# MP9361.net
KiCad netlist of a schematic drawn in EAGLE
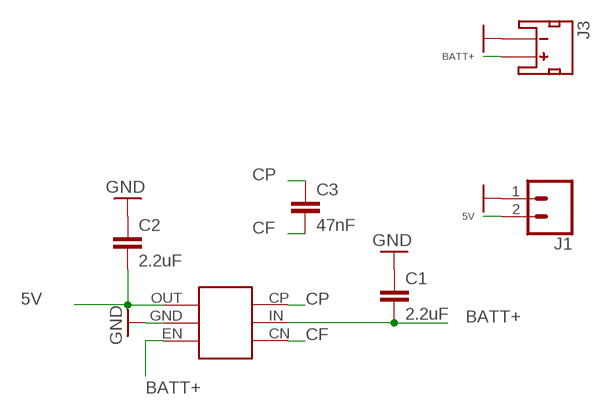
[diagram p0: schematic, sheet 1]

(export (version "E")
  (design (tool "Eeschema 10.0.6"))
  (components
    (comp (ref "C1")
      (value "2.2uF")
      (footprint "eagle-import:0805")
      (libsource (lib "eagle-import") (part "2.2UF-0805-25V-(+80/-20%)"))
    )
    (comp (ref "C2")
      (value "2.2uF")
      (footprint "eagle-import:0805")
      (libsource (lib "eagle-import") (part "2.2UF-0805-25V-(+80/-20%)"))
    )
    (comp (ref "C3")
      (value "47nF")
      (footprint "eagle-import:0603")
      (libsource (lib "eagle-import") (part "47NF-0603-25V-5%"))
    )
    (comp (ref "J1")
      (value "CONN_02PTH4")
      (footprint "eagle-import:1X02_XTRA_BIG")
      (libsource (lib "eagle-import") (part "CONN_02PTH4"))
    )
    (comp (ref "J3")
      (value "Batt Conn")
      (footprint "eagle-import:JST-2-SMD")
      (libsource (lib "eagle-import") (part "JST_2MM_MALE"))
    )
    (comp (ref "U1")
      (value "MP9361")
      (footprint "eagle-import:MP9361")
      (libsource (lib "eagle-import") (part "MP9361"))
    )
  )
  (nets
    (net (code "1") (name "/5V") (class "Default")
      (node (ref "C2") (pin "2") (pinfunction "2_2") (pintype "passive"))
      (node (ref "J1") (pin "2") (pinfunction "2_2") (pintype "passive"))
      (node (ref "U1") (pin "OUT") (pinfunction "OUT_OUT") (pintype "bidirectional"))
    )
    (net (code "2") (name "/BATT+") (class "Default")
      (node (ref "C1") (pin "2") (pinfunction "2_2") (pintype "passive"))
      (node (ref "J3") (pin "2") (pinfunction "+_2") (pintype "bidirectional"))
      (node (ref "U1") (pin "EN") (pinfunction "EN_EN") (pintype "bidirectional"))
      (node (ref "U1") (pin "IN") (pinfunction "IN_IN") (pintype "bidirectional"))
    )
    (net (code "3") (name "/CF") (class "Default")
      (node (ref "C3") (pin "2") (pinfunction "2_2") (pintype "passive"))
      (node (ref "U1") (pin "CN") (pinfunction "CN_CN") (pintype "bidirectional"))
    )
    (net (code "4") (name "/CP") (class "Default")
      (node (ref "C3") (pin "1") (pinfunction "1_1") (pintype "passive"))
      (node (ref "U1") (pin "CP") (pinfunction "CP_CP") (pintype "bidirectional"))
    )
    (net (code "5") (name "GND") (class "Default")
      (node (ref "C1") (pin "1") (pinfunction "1_1") (pintype "passive"))
      (node (ref "C2") (pin "1") (pinfunction "1_1") (pintype "passive"))
      (node (ref "J1") (pin "1") (pinfunction "1_1") (pintype "passive"))
      (node (ref "J3") (pin "1") (pinfunction "-_1") (pintype "bidirectional"))
      (node (ref "U1") (pin "GND") (pinfunction "GND_GND") (pintype "bidirectional"))
    )
    (net (code "6") (name "unconnected-(J3-PAD1-PadNC1)") (class "Default")
      (node (ref "J3") (pin "NC1") (pinfunction "PAD1_NC1") (pintype "bidirectional"))
    )
    (net (code "7") (name "unconnected-(J3-PAD2-PadNC2)") (class "Default")
      (node (ref "J3") (pin "NC2") (pinfunction "PAD2_NC2") (pintype "bidirectional"))
    )
  )
)
